# PWR.net
KiCad netlist of a schematic drawn in Altium Designer
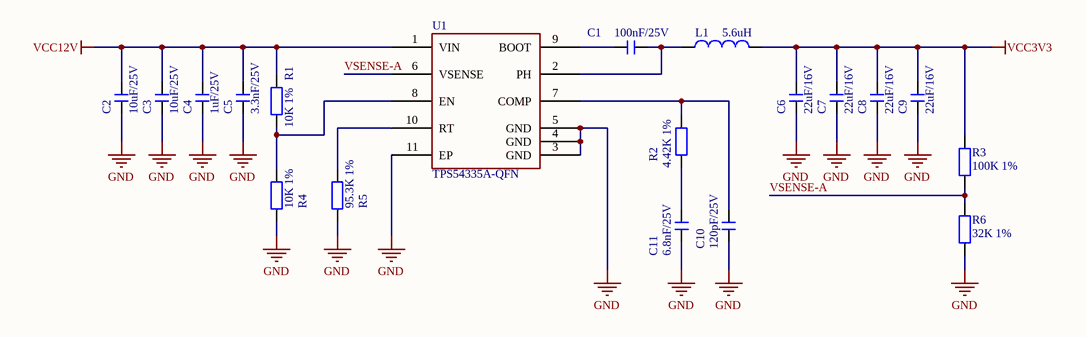
[diagram p0: PWR.SchDoc]

(export (version "E")
  (design (tool "Eeschema 10.0.6"))
  (components
    (comp (ref "C1")
      (value "100nF/25V")
      (footprint "C0603_L")
      (description "无极性贴片电容")
      (fields (field (name "版权归属") "源创客"))
      (libsource (lib "Capacitor") (part "C"))
    )
    (comp (ref "C2")
      (value "10uF/25V")
      (footprint "C0603_L")
      (description "无极性贴片电容")
      (fields (field (name "版权归属") "源创客"))
      (libsource (lib "Capacitor") (part "C"))
    )
    (comp (ref "C3")
      (value "10uF/25V")
      (footprint "C0603_L")
      (description "无极性贴片电容")
      (fields (field (name "版权归属") "源创客"))
      (libsource (lib "Capacitor") (part "C"))
    )
    (comp (ref "C4")
      (value "1uF/25V")
      (footprint "C0603_L")
      (description "无极性贴片电容")
      (fields (field (name "版权归属") "源创客"))
      (libsource (lib "Capacitor") (part "C"))
    )
    (comp (ref "C5")
      (value "3.3nF/25V")
      (footprint "C0603_L")
      (description "无极性贴片电容")
      (fields (field (name "版权归属") "源创客"))
      (libsource (lib "Capacitor") (part "C"))
    )
    (comp (ref "C6")
      (value "22uF/16V")
      (footprint "C0603_L")
      (description "无极性贴片电容")
      (fields (field (name "版权归属") "源创客"))
      (libsource (lib "Capacitor") (part "C"))
    )
    (comp (ref "C7")
      (value "22uF/16V")
      (footprint "C0603_L")
      (description "无极性贴片电容")
      (fields (field (name "版权归属") "源创客"))
      (libsource (lib "Capacitor") (part "C"))
    )
    (comp (ref "C8")
      (value "22uF/16V")
      (footprint "C0603_L")
      (description "无极性贴片电容")
      (fields (field (name "版权归属") "源创客"))
      (libsource (lib "Capacitor") (part "C"))
    )
    (comp (ref "C9")
      (value "22uF/16V")
      (footprint "C0603_L")
      (description "无极性贴片电容")
      (fields (field (name "版权归属") "源创客"))
      (libsource (lib "Capacitor") (part "C"))
    )
    (comp (ref "C10")
      (value "120pF/25V")
      (footprint "C0603_L")
      (description "无极性贴片电容")
      (fields (field (name "版权归属") "源创客"))
      (libsource (lib "Capacitor") (part "C"))
    )
    (comp (ref "C11")
      (value "6.8nF/25V")
      (footprint "C0603_L")
      (description "无极性贴片电容")
      (fields (field (name "版权归属") "源创客"))
      (libsource (lib "Capacitor") (part "C"))
    )
    (comp (ref "L1")
      (value "5.6uH")
      (footprint "NR4020")
      (description "小功率贴片电感")
      (fields (field (name "版权归属") "源创客"))
      (libsource (lib "Inductor") (part "L"))
    )
    (comp (ref "R1")
      (value "10K 1%")
      (footprint "R0603_L")
      (description "贴片电阻")
      (fields (field (name "版权归属") "源创客"))
      (libsource (lib "Resistor") (part "R"))
    )
    (comp (ref "R2")
      (value "4.42K 1%")
      (footprint "R0603_L")
      (description "贴片电阻")
      (fields (field (name "版权归属") "源创客"))
      (libsource (lib "Resistor") (part "R"))
    )
    (comp (ref "R3")
      (value "100K 1%")
      (footprint "R0603_L")
      (description "贴片电阻")
      (fields (field (name "版权归属") "源创客"))
      (libsource (lib "Resistor") (part "R"))
    )
    (comp (ref "R4")
      (value "10K 1%")
      (footprint "R0603_L")
      (description "贴片电阻")
      (fields (field (name "版权归属") "源创客"))
      (libsource (lib "Resistor") (part "R"))
    )
    (comp (ref "R5")
      (value "95.3K 1%")
      (footprint "R0603_L")
      (description "贴片电阻")
      (fields (field (name "版权归属") "源创客"))
      (libsource (lib "Resistor") (part "R"))
    )
    (comp (ref "R6")
      (value "32K 1%")
      (footprint "R0603_L")
      (description "贴片电阻")
      (fields (field (name "版权归属") "源创客"))
      (libsource (lib "Resistor") (part "R"))
    )
    (comp (ref "U1")
      (value "TPS54335A-QFN")
      (footprint "VSON-10_L3.0-W3.0-P0.50-TL-EP")
      (description "BUCK")
      (libsource (lib "DCDC Convert") (part "TPS54335A-QFN"))
    )
  )
  (nets
    (net (code "1") (name "/VSENSE-A") (class "Default")
      (node (ref "R3") (pin "2") (pinfunction "2_2") (pintype "passive"))
      (node (ref "R6") (pin "1") (pinfunction "1_1") (pintype "passive"))
      (node (ref "U1") (pin "6") (pinfunction "VSENSE_6") (pintype "passive"))
    )
    (net (code "2") (name "GND") (class "Default")
      (node (ref "C10") (pin "1") (pinfunction "1_1") (pintype "passive"))
      (node (ref "C11") (pin "1") (pinfunction "1_1") (pintype "passive"))
      (node (ref "C2") (pin "1") (pinfunction "1_1") (pintype "passive"))
      (node (ref "C3") (pin "1") (pinfunction "1_1") (pintype "passive"))
      (node (ref "C4") (pin "1") (pinfunction "1_1") (pintype "passive"))
      (node (ref "C5") (pin "1") (pinfunction "1_1") (pintype "passive"))
      (node (ref "C6") (pin "1") (pinfunction "1_1") (pintype "passive"))
      (node (ref "C7") (pin "1") (pinfunction "1_1") (pintype "passive"))
      (node (ref "C8") (pin "1") (pinfunction "1_1") (pintype "passive"))
      (node (ref "C9") (pin "1") (pinfunction "1_1") (pintype "passive"))
      (node (ref "R4") (pin "2") (pinfunction "2_2") (pintype "passive"))
      (node (ref "R5") (pin "2") (pinfunction "2_2") (pintype "passive"))
      (node (ref "R6") (pin "2") (pinfunction "2_2") (pintype "passive"))
      (node (ref "U1") (pin "11") (pinfunction "EP_11") (pintype "passive"))
      (node (ref "U1") (pin "3") (pinfunction "GND_3") (pintype "passive"))
      (node (ref "U1") (pin "4") (pinfunction "GND_4") (pintype "passive"))
      (node (ref "U1") (pin "5") (pinfunction "GND_5") (pintype "passive"))
    )
    (net (code "3") (name "Net-(C11-Pad2)") (class "Default")
      (node (ref "C11") (pin "2") (pinfunction "2_2") (pintype "passive"))
      (node (ref "R2") (pin "2") (pinfunction "2_2") (pintype "passive"))
    )
    (net (code "4") (name "Net-(U1-BOOT)") (class "Default")
      (node (ref "C1") (pin "2") (pinfunction "2_2") (pintype "passive"))
      (node (ref "U1") (pin "9") (pinfunction "BOOT_9") (pintype "passive"))
    )
    (net (code "5") (name "Net-(U1-COMP)") (class "Default")
      (node (ref "C10") (pin "2") (pinfunction "2_2") (pintype "passive"))
      (node (ref "R2") (pin "1") (pinfunction "1_1") (pintype "passive"))
      (node (ref "U1") (pin "7") (pinfunction "COMP_7") (pintype "passive"))
    )
    (net (code "6") (name "Net-(U1-EN)") (class "Default")
      (node (ref "R1") (pin "2") (pinfunction "2_2") (pintype "passive"))
      (node (ref "R4") (pin "1") (pinfunction "1_1") (pintype "passive"))
      (node (ref "U1") (pin "8") (pinfunction "EN_8") (pintype "passive"))
    )
    (net (code "7") (name "Net-(U1-PH)") (class "Default")
      (node (ref "C1") (pin "1") (pinfunction "1_1") (pintype "passive"))
      (node (ref "L1") (pin "1") (pinfunction "1_1") (pintype "passive"))
      (node (ref "U1") (pin "2") (pinfunction "PH_2") (pintype "passive"))
    )
    (net (code "8") (name "Net-(U1-RT)") (class "Default")
      (node (ref "R5") (pin "1") (pinfunction "1_1") (pintype "passive"))
      (node (ref "U1") (pin "10") (pinfunction "RT_10") (pintype "passive"))
    )
    (net (code "9") (name "VCC3V3") (class "Default")
      (node (ref "C6") (pin "2") (pinfunction "2_2") (pintype "passive"))
      (node (ref "C7") (pin "2") (pinfunction "2_2") (pintype "passive"))
      (node (ref "C8") (pin "2") (pinfunction "2_2") (pintype "passive"))
      (node (ref "C9") (pin "2") (pinfunction "2_2") (pintype "passive"))
      (node (ref "L1") (pin "2") (pinfunction "2_2") (pintype "passive"))
      (node (ref "R3") (pin "1") (pinfunction "1_1") (pintype "passive"))
    )
    (net (code "10") (name "VCC12V") (class "Default")
      (node (ref "C2") (pin "2") (pinfunction "2_2") (pintype "passive"))
      (node (ref "C3") (pin "2") (pinfunction "2_2") (pintype "passive"))
      (node (ref "C4") (pin "2") (pinfunction "2_2") (pintype "passive"))
      (node (ref "C5") (pin "2") (pinfunction "2_2") (pintype "passive"))
      (node (ref "R1") (pin "1") (pinfunction "1_1") (pintype "passive"))
      (node (ref "U1") (pin "1") (pinfunction "VIN_1") (pintype "passive"))
    )
  )
)
